# MCU-Power.net
KiCad netlist of a schematic drawn in Altium Designer
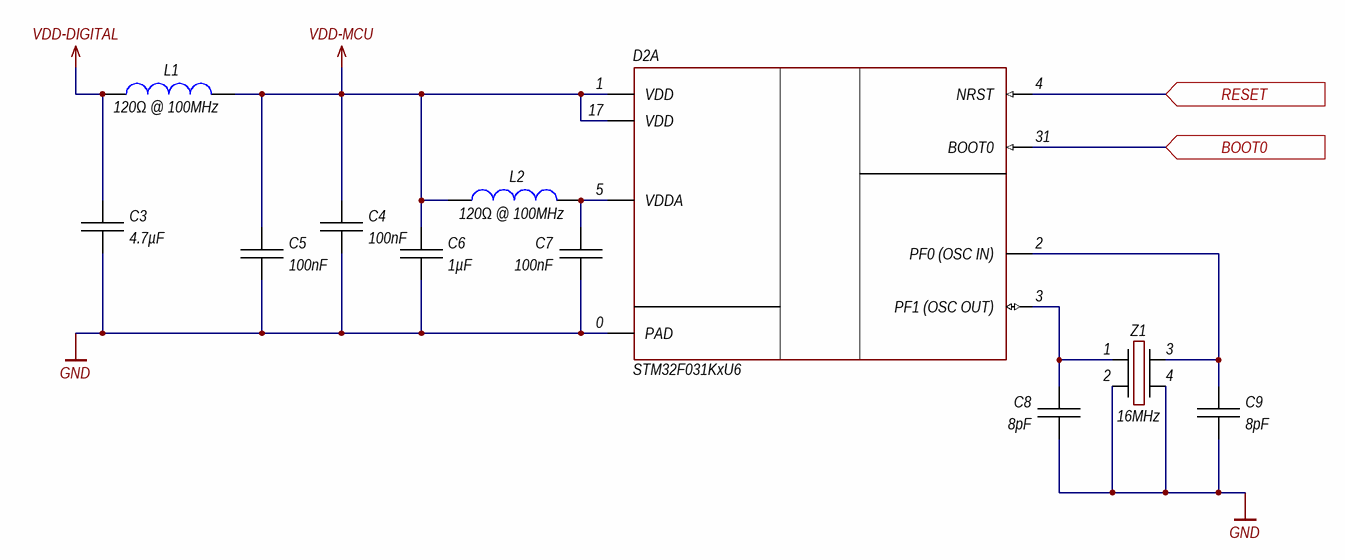
[diagram p0: MCU-Power.SchDoc]

(export (version "E")
  (design (tool "Eeschema 10.0.6"))
  (components
    (comp (ref "C3") (value "4.7µF") (footprint "CH0402C") (libsource (lib "Discrete") (part "Capacitor")))
    (comp (ref "C4") (value "100nF") (footprint "CH0402C") (libsource (lib "Discrete") (part "Capacitor")))
    (comp (ref "C5") (value "100nF") (footprint "CH0402C") (libsource (lib "Discrete") (part "Capacitor")))
    (comp (ref "C6") (value "1µF") (footprint "CH0402C") (libsource (lib "Discrete") (part "Capacitor")))
    (comp (ref "C7") (value "100nF") (footprint "CH0402C") (libsource (lib "Discrete") (part "Capacitor")))
    (comp (ref "C8") (value "8pF") (footprint "CH0402C") (libsource (lib "Discrete") (part "Capacitor")))
    (comp (ref "C9") (value "8pF") (footprint "CH0402C") (libsource (lib "Discrete") (part "Capacitor")))
    (comp (ref "D2")
      (value "STM32F031KxU6")
      (footprint "32-UFQFPN")
      (description "STM32, Cortex-M0")
      (fields (field (name "MANUFACTURER") "ST Microelectronics"))
      (libsource (lib "Digital") (part "STM32F031KxU6"))
    )
    (comp (ref "L1")
      (value "120Ω @ 100MHz")
      (footprint "CH0402L")
      (libsource (lib "Discrete") (part "Inductor"))
    )
    (comp (ref "L2")
      (value "120Ω @ 100MHz")
      (footprint "CH0402L")
      (libsource (lib "Discrete") (part "Inductor"))
    )
    (comp (ref "Z1") (value "16MHz") (footprint "OSC: 2520") (libsource (lib "Discrete") (part "Generator")))
  )
  (nets
    (net (code "1") (name "/BOOT0") (class "Default")
      (node (ref "D2") (pin "31") (pinfunction "BOOT0_31") (pintype "input"))
    )
    (net (code "2") (name "/RESET") (class "Default")
      (node (ref "D2") (pin "4") (pinfunction "NRST_4") (pintype "input"))
    )
    (net (code "3") (name "GND") (class "Default")
      (node (ref "C3") (pin "1") (pinfunction "1_1") (pintype "passive"))
      (node (ref "C4") (pin "1") (pinfunction "1_1") (pintype "passive"))
      (node (ref "C5") (pin "1") (pinfunction "1_1") (pintype "passive"))
      (node (ref "C6") (pin "1") (pinfunction "1_1") (pintype "passive"))
      (node (ref "C7") (pin "1") (pinfunction "1_1") (pintype "passive"))
      (node (ref "C8") (pin "1") (pinfunction "1_1") (pintype "passive"))
      (node (ref "C9") (pin "1") (pinfunction "1_1") (pintype "passive"))
      (node (ref "D2") (pin "0") (pinfunction "PAD_0") (pintype "power_in"))
      (node (ref "Z1") (pin "2") (pinfunction "2_2") (pintype "passive"))
      (node (ref "Z1") (pin "4") (pinfunction "4_4") (pintype "passive"))
    )
    (net (code "4") (name "Net-(D2A-PF0_(OSC_IN))") (class "Default")
      (node (ref "C9") (pin "2") (pinfunction "2_2") (pintype "passive"))
      (node (ref "D2") (pin "2") (pinfunction "PF0_(OSC_IN)_2") (pintype "power_in"))
      (node (ref "Z1") (pin "3") (pinfunction "3_3") (pintype "passive"))
    )
    (net (code "5") (name "Net-(D2A-PF1_(OSC_OUT))") (class "Default")
      (node (ref "C8") (pin "2") (pinfunction "2_2") (pintype "passive"))
      (node (ref "D2") (pin "3") (pinfunction "PF1_(OSC_OUT)_3") (pintype "bidirectional"))
      (node (ref "Z1") (pin "1") (pinfunction "1_1") (pintype "passive"))
    )
    (net (code "6") (name "Net-(D2A-VDDA)") (class "Default")
      (node (ref "C7") (pin "2") (pinfunction "2_2") (pintype "passive"))
      (node (ref "D2") (pin "5") (pinfunction "VDDA_5") (pintype "power_in"))
      (node (ref "L2") (pin "1") (pinfunction "1_1") (pintype "passive"))
    )
    (net (code "7") (name "VDD-DIGITAL") (class "Default")
      (node (ref "C3") (pin "2") (pinfunction "2_2") (pintype "passive"))
      (node (ref "L1") (pin "2") (pinfunction "2_2") (pintype "passive"))
    )
    (net (code "8") (name "VDD-MCU") (class "Default")
      (node (ref "C4") (pin "2") (pinfunction "2_2") (pintype "passive"))
      (node (ref "C5") (pin "2") (pinfunction "2_2") (pintype "passive"))
      (node (ref "C6") (pin "2") (pinfunction "2_2") (pintype "passive"))
      (node (ref "D2") (pin "1") (pinfunction "VDD_1") (pintype "power_in"))
      (node (ref "D2") (pin "17") (pinfunction "VDD_17") (pintype "power_in"))
      (node (ref "L1") (pin "1") (pinfunction "1_1") (pintype "passive"))
      (node (ref "L2") (pin "2") (pinfunction "2_2") (pintype "passive"))
    )
  )
)
